# SW6124_A_B_C_Lighting_LED.net
KiCad netlist of a schematic drawn in Altium Designer
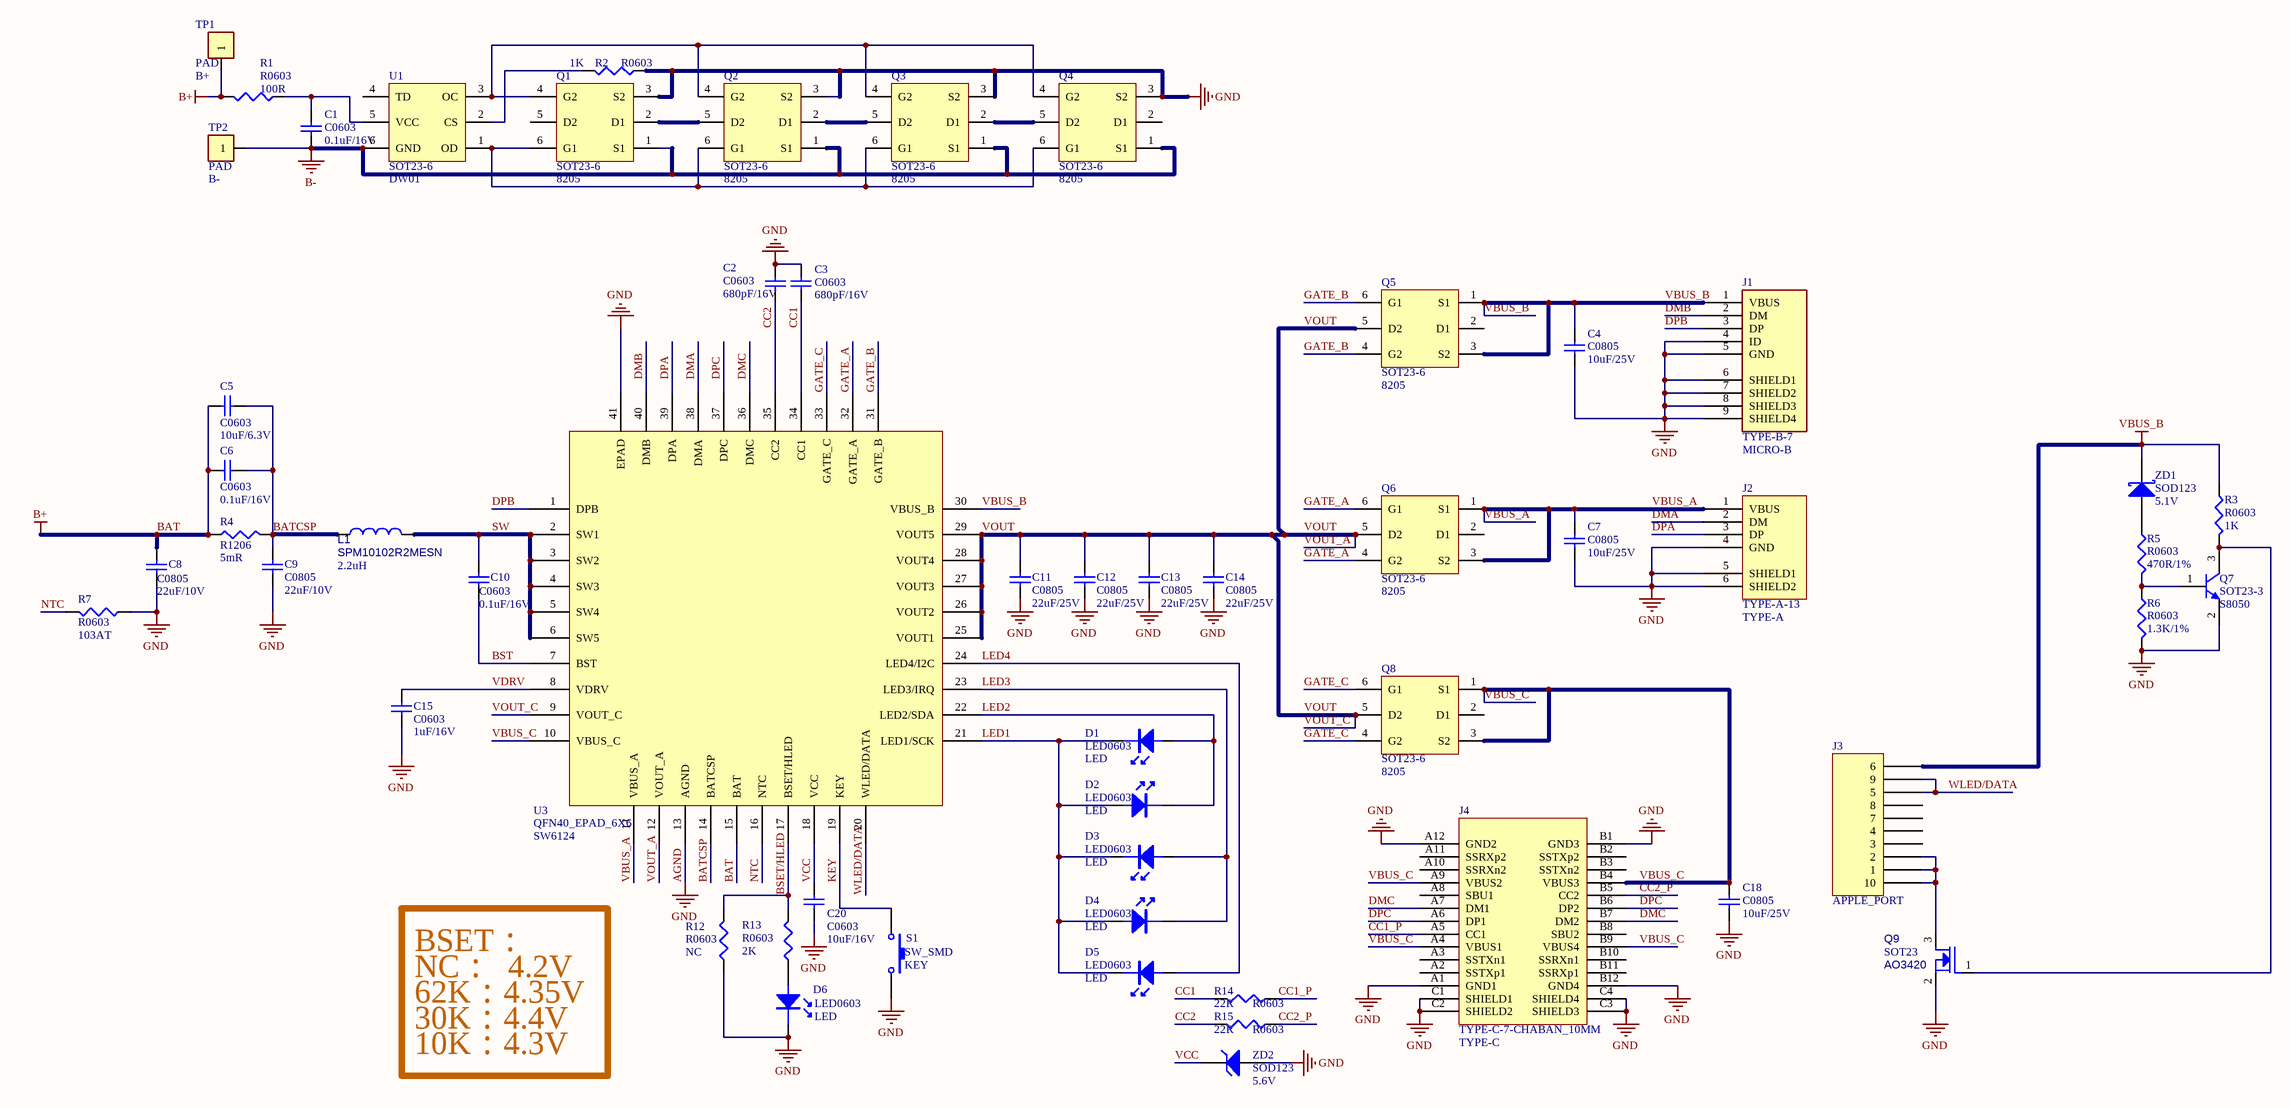
[diagram p0: SW6124+A+B+C+内部解密Lighting+LED.SchDoc]

(export (version "E")
  (design (tool "Eeschema 10.0.6"))
  (components
    (comp (ref "C1")
      (value "C0603")
      (footprint "C0603")
      (description "Capacitor")
      (fields (field (name "ALTIUM_VALUE") "0.1uF/16V") (field (name "PUBLISHER") "Altium Limited"))
      (libsource (lib "*") (part "Cap"))
    )
    (comp (ref "C2")
      (value "C0603")
      (footprint "C0603")
      (description "Capacitor")
      (fields (field (name "ALTIUM_VALUE") "680pF/16V") (field (name "PUBLISHER") "Altium Limited"))
      (libsource (lib "*") (part "CAP0603"))
    )
    (comp (ref "C3")
      (value "C0603")
      (footprint "C0603")
      (description "Capacitor")
      (fields (field (name "ALTIUM_VALUE") "680pF/16V") (field (name "PUBLISHER") "Altium Limited"))
      (libsource (lib "*") (part "CAP0603"))
    )
    (comp (ref "C4")
      (value "C0805")
      (footprint "C0805")
      (description "Capacitor")
      (fields (field (name "ALTIUM_VALUE") "10uF/25V") (field (name "PUBLISHER") "Altium Limited"))
      (libsource (lib "*") (part "CAP0603"))
    )
    (comp (ref "C5")
      (value "C0603")
      (footprint "C0603")
      (description "Capacitor")
      (fields (field (name "ALTIUM_VALUE") "10uF/6.3V") (field (name "PUBLISHER") "Altium Limited"))
      (libsource (lib "*") (part "CAP0603"))
    )
    (comp (ref "C6")
      (value "C0603")
      (footprint "C0603")
      (description "Capacitor")
      (fields (field (name "ALTIUM_VALUE") "0.1uF/16V") (field (name "PUBLISHER") "Altium Limited"))
      (libsource (lib "*") (part "CAP0603"))
    )
    (comp (ref "C7")
      (value "C0805")
      (footprint "C0805")
      (description "Capacitor")
      (fields (field (name "ALTIUM_VALUE") "10uF/25V") (field (name "PUBLISHER") "Altium Limited"))
      (libsource (lib "*") (part "CAP0603"))
    )
    (comp (ref "C8")
      (value "C0805")
      (footprint "C0805")
      (description "Capacitor")
      (fields (field (name "ALTIUM_VALUE") "22uF/10V") (field (name "PUBLISHER") "Altium Limited"))
      (libsource (lib "*") (part "CAP0805"))
    )
    (comp (ref "C9")
      (value "C0805")
      (footprint "C0805")
      (description "Capacitor")
      (fields (field (name "ALTIUM_VALUE") "22uF/10V") (field (name "PUBLISHER") "Altium Limited"))
      (libsource (lib "*") (part "CAP0805"))
    )
    (comp (ref "C10")
      (value "C0603")
      (footprint "C0603")
      (description "Capacitor")
      (fields (field (name "ALTIUM_VALUE") "0.1uF/16V") (field (name "PUBLISHER") "Altium Limited"))
      (libsource (lib "*") (part "CAP0603"))
    )
    (comp (ref "C11")
      (value "C0805")
      (footprint "C0805")
      (description "Capacitor")
      (fields (field (name "ALTIUM_VALUE") "22uF/25V") (field (name "PUBLISHER") "Altium Limited"))
      (libsource (lib "*") (part "CAP0805"))
    )
    (comp (ref "C12")
      (value "C0805")
      (footprint "C0805")
      (description "Capacitor")
      (fields (field (name "ALTIUM_VALUE") "22uF/25V") (field (name "PUBLISHER") "Altium Limited"))
      (libsource (lib "*") (part "CAP0805"))
    )
    (comp (ref "C13")
      (value "C0805")
      (footprint "C0805")
      (description "Capacitor")
      (fields (field (name "ALTIUM_VALUE") "22uF/25V") (field (name "PUBLISHER") "Altium Limited"))
      (libsource (lib "*") (part "CAP0805"))
    )
    (comp (ref "C14")
      (value "C0805")
      (footprint "C0805")
      (description "Capacitor")
      (fields (field (name "ALTIUM_VALUE") "22uF/25V") (field (name "PUBLISHER") "Altium Limited"))
      (libsource (lib "*") (part "CAP0805"))
    )
    (comp (ref "C15")
      (value "C0603")
      (footprint "C0603")
      (description "Capacitor")
      (fields (field (name "ALTIUM_VALUE") "1uF/16V") (field (name "PUBLISHER") "Altium Limited"))
      (libsource (lib "*") (part "CAP0603"))
    )
    (comp (ref "C18")
      (value "C0805")
      (footprint "C0805")
      (description "Capacitor")
      (fields (field (name "ALTIUM_VALUE") "10uF/25V") (field (name "PUBLISHER") "Altium Limited"))
      (libsource (lib "*") (part "CAP0603"))
    )
    (comp (ref "C20")
      (value "C0603")
      (footprint "C0603")
      (description "Capacitor")
      (fields (field (name "ALTIUM_VALUE") "10uF/16V") (field (name "PUBLISHER") "Altium Limited"))
      (libsource (lib "*") (part "CAP0603"))
    )
    (comp (ref "D1") (value "LED") (footprint "LED0603") (libsource (lib "*") (part "LED")))
    (comp (ref "D2") (value "LED") (footprint "LED0603") (libsource (lib "*") (part "LED")))
    (comp (ref "D3") (value "LED") (footprint "LED0603") (libsource (lib "*") (part "LED")))
    (comp (ref "D4") (value "LED") (footprint "LED0603") (libsource (lib "*") (part "LED")))
    (comp (ref "D5") (value "LED") (footprint "LED0603") (libsource (lib "*") (part "LED")))
    (comp (ref "D6") (value "LED") (footprint "LED0603") (libsource (lib "*") (part "LED")))
    (comp (ref "J1")
      (value "MICRO-B")
      (footprint "TYPE-B-7")
      (fields (field (name "FOOTPRINTF") "TYPE-B-7") (field (name "Comment") "USB_MICRO_B"))
      (libsource (lib "*") (part "USB_MICRO_B"))
    )
    (comp (ref "J2")
      (value "TYPE-A")
      (footprint "TYPE-A-13")
      (fields (field (name "FOOTPRINF") "TYPE-A-13") (field (name "Comment") "TYPE-A-1"))
      (libsource (lib "*") (part "TYPE-A-1"))
    )
    (comp (ref "J3") (value "APPLE_PORT") (libsource (lib "TEST") (part "APPLE_PORT")))
    (comp (ref "J4")
      (value "TYPE-C")
      (footprint "TYPE-C-7-CHABAN_10MM")
      (libsource (lib "*") (part "TYPE-C"))
    )
    (comp (ref "L1")
      (value "SPM10102R2MESN")
      (footprint "INDUCTOR_SPM1010")
      (fields (field (name "ALTIUM_VALUE") "2.2uH"))
      (libsource (lib "*") (part "INDUCTOR"))
    )
    (comp (ref "Q1")
      (value "8205")
      (footprint "SOT23-6")
      (fields (field (name "FOOTPRINF") "SOT23-6"))
      (libsource (lib "*") (part "8205B"))
    )
    (comp (ref "Q2")
      (value "8205")
      (footprint "SOT23-6")
      (fields (field (name "FOOTPRINF") "SOT23-6"))
      (libsource (lib "*") (part "8205B"))
    )
    (comp (ref "Q3")
      (value "8205")
      (footprint "SOT23-6")
      (fields (field (name "FOOTPRINF") "SOT23-6"))
      (libsource (lib "*") (part "8205B"))
    )
    (comp (ref "Q4")
      (value "8205")
      (footprint "SOT23-6")
      (fields (field (name "FOOTPRINF") "SOT23-6"))
      (libsource (lib "*") (part "8205B"))
    )
    (comp (ref "Q5")
      (value "8205")
      (footprint "SOT23-6")
      (fields (field (name "FOOTPRINF") "SOT23-6"))
      (libsource (lib "") (part "8205B_1"))
    )
    (comp (ref "Q6")
      (value "8205")
      (footprint "SOT23-6")
      (fields (field (name "FOOTPRINF") "SOT23-6"))
      (libsource (lib "") (part "8205B_1"))
    )
    (comp (ref "Q7")
      (value "S8050")
      (footprint "SOT23-3")
      (description "NPN General Purpose Amplifier")
      (fields (field (name "PUBLISHER") "Altium Limited"))
      (libsource (lib "Miscellaneous Devices") (part "2N3904"))
    )
    (comp (ref "Q8")
      (value "8205")
      (footprint "SOT23-6")
      (fields (field (name "FOOTPRINF") "SOT23-6"))
      (libsource (lib "") (part "8205B_1"))
    )
    (comp (ref "Q9") (value "AO3420") (footprint "SOT23") (libsource (lib "智融科技有限公司原理图库") (part "MOSFET_N")))
    (comp (ref "R1")
      (value "R0603")
      (footprint "R0603")
      (description "Resistor")
      (fields (field (name "ALTIUM_VALUE") "100R") (field (name "PUBLISHER") "Altium Limited"))
      (libsource (lib "*") (part "Res3"))
    )
    (comp (ref "R2")
      (value "R0603")
      (footprint "R0603")
      (description "Resistor")
      (fields (field (name "ALTIUM_VALUE") "1K") (field (name "PUBLISHER") "Altium Limited"))
      (libsource (lib "*") (part "Res3"))
    )
    (comp (ref "R3")
      (value "R0603")
      (footprint "R0603")
      (description "Resistor")
      (fields (field (name "ALTIUM_VALUE") "1K") (field (name "PUBLISHER") "Altium Limited"))
      (libsource (lib "Miscellaneous Devices") (part "Res3"))
    )
    (comp (ref "R4")
      (value "R1206")
      (footprint "R1206")
      (description "Resistor")
      (fields (field (name "ALTIUM_VALUE") "5mR") (field (name "PUBLISHER") "Altium Limited"))
      (libsource (lib "*") (part "RES"))
    )
    (comp (ref "R5")
      (value "R0603")
      (footprint "R0603")
      (description "Resistor")
      (fields (field (name "ALTIUM_VALUE") "470R/1%") (field (name "PUBLISHER") "Altium Limited"))
      (libsource (lib "Miscellaneous Devices") (part "Res3"))
    )
    (comp (ref "R6")
      (value "R0603")
      (footprint "R0603")
      (description "Resistor")
      (fields (field (name "ALTIUM_VALUE") "1.3K/1%") (field (name "PUBLISHER") "Altium Limited"))
      (libsource (lib "Miscellaneous Devices") (part "Res3"))
    )
    (comp (ref "R7")
      (value "R0603")
      (footprint "R0603")
      (description "Resistor")
      (fields (field (name "ALTIUM_VALUE") "103AT") (field (name "PUBLISHER") "Altium Limited"))
      (libsource (lib "*") (part "RES"))
    )
    (comp (ref "R12")
      (value "R0603")
      (footprint "R0603")
      (description "Resistor")
      (fields (field (name "ALTIUM_VALUE") "NC") (field (name "PUBLISHER") "Altium Limited"))
      (libsource (lib "*") (part "RES"))
    )
    (comp (ref "R13")
      (value "R0603")
      (footprint "R0603")
      (description "Resistor")
      (fields (field (name "ALTIUM_VALUE") "2K") (field (name "PUBLISHER") "Altium Limited"))
      (libsource (lib "*") (part "RES"))
    )
    (comp (ref "R14")
      (value "R0603")
      (footprint "R0603")
      (description "Resistor")
      (fields (field (name "ALTIUM_VALUE") "22R") (field (name "PUBLISHER") "Altium Limited"))
      (libsource (lib "*") (part "RES"))
    )
    (comp (ref "R15")
      (value "R0603")
      (footprint "R0603")
      (description "Resistor")
      (fields (field (name "ALTIUM_VALUE") "22R") (field (name "PUBLISHER") "Altium Limited"))
      (libsource (lib "*") (part "RES"))
    )
    (comp (ref "S1")
      (value "KEY")
      (footprint "SW_SMD")
      (fields (field (name "FOOTPRINF") "SW_SMD"))
      (libsource (lib "*") (part "SW K"))
    )
    (comp (ref "TP1") (value "B+") (footprint "PAD") (libsource (lib "*") (part "Test Point")))
    (comp (ref "TP2") (value "B-") (footprint "PAD") (libsource (lib "") (part "Test Point_1")))
    (comp (ref "U1")
      (value "DW01")
      (footprint "SOT23-6")
      (fields (field (name "FOOTPRINF") "SOT23-6"))
      (libsource (lib "*") (part "DW01"))
    )
    (comp (ref "U3")
      (value "SW6124")
      (footprint "QFN40_EPAD_6X6")
      (libsource (lib "TEST") (part "SW6106_AFC"))
    )
    (comp (ref "ZD1")
      (value "5.1V")
      (footprint "SOD123")
      (description "Schottky Rectifier")
      (fields (field (name "Comment") "Diode 11DQ03") (field (name "PUBLISHER") "Altium Limited"))
      (libsource (lib "Miscellaneous Devices") (part "Diode 11DQ03"))
    )
    (comp (ref "ZD2")
      (value "SOD123")
      (footprint "SOD-123")
      (description "Zener Diode")
      (fields (field (name "ALTIUM_UNNAMED_1") "5.6V"))
      (libsource (lib "Miscellaneous Devices") (part "D Zener"))
    )
  )
  (nets
    (net (code "1") (name "/BATCSP") (class "Default")
      (node (ref "C5") (pin "2") (pinfunction "2_2") (pintype "passive"))
      (node (ref "C6") (pin "2") (pinfunction "2_2") (pintype "passive"))
      (node (ref "C9") (pin "2") (pinfunction "2_2") (pintype "passive"))
      (node (ref "L1") (pin "1") (pinfunction "1_1") (pintype "passive"))
      (node (ref "R4") (pin "2") (pinfunction "2_2") (pintype "passive"))
      (node (ref "U3") (pin "14") (pinfunction "BATCSP_14") (pintype "passive"))
    )
    (net (code "2") (name "/BSET{slash}HLED") (class "Default")
      (node (ref "R12") (pin "2") (pinfunction "2_2") (pintype "passive"))
      (node (ref "R13") (pin "2") (pinfunction "2_2") (pintype "passive"))
      (node (ref "U3") (pin "17") (pinfunction "BSET/HLED_17") (pintype "passive"))
    )
    (net (code "3") (name "/BST") (class "Default")
      (node (ref "C10") (pin "1") (pinfunction "1_1") (pintype "passive"))
      (node (ref "U3") (pin "7") (pinfunction "BST_7") (pintype "passive"))
    )
    (net (code "4") (name "/CC1") (class "Default")
      (node (ref "C3") (pin "1") (pinfunction "1_1") (pintype "passive"))
      (node (ref "R14") (pin "2") (pinfunction "2_2") (pintype "passive"))
      (node (ref "U3") (pin "34") (pinfunction "CC1_34") (pintype "passive"))
    )
    (net (code "5") (name "/CC1_P") (class "Default")
      (node (ref "J4") (pin "A5") (pinfunction "CC1_A5") (pintype "passive"))
      (node (ref "R14") (pin "1") (pinfunction "1_1") (pintype "passive"))
    )
    (net (code "6") (name "/CC2") (class "Default")
      (node (ref "C2") (pin "1") (pinfunction "1_1") (pintype "passive"))
      (node (ref "R15") (pin "2") (pinfunction "2_2") (pintype "passive"))
      (node (ref "U3") (pin "35") (pinfunction "CC2_35") (pintype "passive"))
    )
    (net (code "7") (name "/CC2_P") (class "Default")
      (node (ref "J4") (pin "B5") (pinfunction "CC2_B5") (pintype "passive"))
      (node (ref "R15") (pin "1") (pinfunction "1_1") (pintype "passive"))
    )
    (net (code "8") (name "/DMA") (class "Default")
      (node (ref "J2") (pin "2") (pinfunction "DM_2") (pintype "passive"))
      (node (ref "U3") (pin "38") (pinfunction "DMA_38") (pintype "passive"))
    )
    (net (code "9") (name "/DMB") (class "Default")
      (node (ref "J1") (pin "2") (pinfunction "DM_2") (pintype "passive"))
      (node (ref "U3") (pin "40") (pinfunction "DMB_40") (pintype "passive"))
    )
    (net (code "10") (name "/DMC") (class "Default")
      (node (ref "J4") (pin "A7") (pinfunction "DM1_A7") (pintype "passive"))
      (node (ref "J4") (pin "B7") (pinfunction "DM2_B7") (pintype "passive"))
      (node (ref "U3") (pin "36") (pinfunction "DMC_36") (pintype "passive"))
    )
    (net (code "11") (name "/DPA") (class "Default")
      (node (ref "J2") (pin "3") (pinfunction "DP_3") (pintype "passive"))
      (node (ref "U3") (pin "39") (pinfunction "DPA_39") (pintype "passive"))
    )
    (net (code "12") (name "/DPB") (class "Default")
      (node (ref "J1") (pin "3") (pinfunction "DP_3") (pintype "passive"))
      (node (ref "U3") (pin "1") (pinfunction "DPB_1") (pintype "passive"))
    )
    (net (code "13") (name "/DPC") (class "Default")
      (node (ref "J4") (pin "A6") (pinfunction "DP1_A6") (pintype "passive"))
      (node (ref "J4") (pin "B6") (pinfunction "DP2_B6") (pintype "passive"))
      (node (ref "U3") (pin "37") (pinfunction "DPC_37") (pintype "passive"))
    )
    (net (code "14") (name "/GATE_A") (class "Default")
      (node (ref "Q6") (pin "4") (pinfunction "G2_4") (pintype "passive"))
      (node (ref "Q6") (pin "6") (pinfunction "G1_6") (pintype "passive"))
      (node (ref "U3") (pin "32") (pinfunction "GATE_A_32") (pintype "passive"))
    )
    (net (code "15") (name "/GATE_B") (class "Default")
      (node (ref "Q5") (pin "4") (pinfunction "G2_4") (pintype "passive"))
      (node (ref "Q5") (pin "6") (pinfunction "G1_6") (pintype "passive"))
      (node (ref "U3") (pin "31") (pinfunction "GATE_B_31") (pintype "passive"))
    )
    (net (code "16") (name "/GATE_C") (class "Default")
      (node (ref "Q8") (pin "4") (pinfunction "G2_4") (pintype "passive"))
      (node (ref "Q8") (pin "6") (pinfunction "G1_6") (pintype "passive"))
      (node (ref "U3") (pin "33") (pinfunction "GATE_C_33") (pintype "passive"))
    )
    (net (code "17") (name "/KEY") (class "Default")
      (node (ref "S1") (pin "1") (pinfunction "1_1") (pintype "passive"))
      (node (ref "U3") (pin "19") (pinfunction "KEY_19") (pintype "passive"))
    )
    (net (code "18") (name "/LED1") (class "Default")
      (node (ref "D1") (pin "2") (pinfunction "K_2") (pintype "passive"))
      (node (ref "D2") (pin "1") (pinfunction "A_1") (pintype "passive"))
      (node (ref "D3") (pin "2") (pinfunction "K_2") (pintype "passive"))
      (node (ref "D4") (pin "1") (pinfunction "A_1") (pintype "passive"))
      (node (ref "D5") (pin "2") (pinfunction "K_2") (pintype "passive"))
      (node (ref "U3") (pin "21") (pinfunction "LED1/SCK_21") (pintype "passive"))
    )
    (net (code "19") (name "/LED2") (class "Default")
      (node (ref "D1") (pin "1") (pinfunction "A_1") (pintype "passive"))
      (node (ref "D2") (pin "2") (pinfunction "K_2") (pintype "passive"))
      (node (ref "U3") (pin "22") (pinfunction "LED2/SDA_22") (pintype "passive"))
    )
    (net (code "20") (name "/LED3") (class "Default")
      (node (ref "D3") (pin "1") (pinfunction "A_1") (pintype "passive"))
      (node (ref "D4") (pin "2") (pinfunction "K_2") (pintype "passive"))
      (node (ref "U3") (pin "23") (pinfunction "LED3/IRQ_23") (pintype "passive"))
    )
    (net (code "21") (name "/LED4") (class "Default")
      (node (ref "D5") (pin "1") (pinfunction "A_1") (pintype "passive"))
      (node (ref "U3") (pin "24") (pinfunction "LED4/I2C_24") (pintype "passive"))
    )
    (net (code "22") (name "/NTC") (class "Default")
      (node (ref "R7") (pin "2") (pinfunction "2_2") (pintype "passive"))
      (node (ref "U3") (pin "16") (pinfunction "NTC_16") (pintype "passive"))
    )
    (net (code "23") (name "/SW") (class "Default")
      (node (ref "C10") (pin "2") (pinfunction "2_2") (pintype "passive"))
      (node (ref "L1") (pin "2") (pinfunction "2_2") (pintype "passive"))
      (node (ref "U3") (pin "2") (pinfunction "SW1_2") (pintype "passive"))
      (node (ref "U3") (pin "3") (pinfunction "SW2_3") (pintype "passive"))
      (node (ref "U3") (pin "4") (pinfunction "SW3_4") (pintype "passive"))
      (node (ref "U3") (pin "5") (pinfunction "SW4_5") (pintype "passive"))
      (node (ref "U3") (pin "6") (pinfunction "SW5_6") (pintype "passive"))
    )
    (net (code "24") (name "/VBUS_A") (class "Default")
      (node (ref "C7") (pin "2") (pinfunction "2_2") (pintype "passive"))
      (node (ref "J2") (pin "1") (pinfunction "VBUS_1") (pintype "passive"))
      (node (ref "Q6") (pin "1") (pinfunction "S1_1") (pintype "passive"))
      (node (ref "Q6") (pin "3") (pinfunction "S2_3") (pintype "passive"))
      (node (ref "U3") (pin "11") (pinfunction "VBUS_A_11") (pintype "passive"))
    )
    (net (code "25") (name "/VBUS_C") (class "Default")
      (node (ref "C18") (pin "2") (pinfunction "2_2") (pintype "passive"))
      (node (ref "J4") (pin "A4") (pinfunction "VBUS1_A4") (pintype "passive"))
      (node (ref "J4") (pin "A9") (pinfunction "VBUS2_A9") (pintype "passive"))
      (node (ref "J4") (pin "B4") (pinfunction "VBUS3_B4") (pintype "passive"))
      (node (ref "J4") (pin "B9") (pinfunction "VBUS4_B9") (pintype "passive"))
      (node (ref "Q8") (pin "1") (pinfunction "S1_1") (pintype "passive"))
      (node (ref "Q8") (pin "3") (pinfunction "S2_3") (pintype "passive"))
      (node (ref "U3") (pin "10") (pinfunction "VBUS_C_10") (pintype "passive"))
    )
    (net (code "26") (name "/VCC") (class "Default")
      (node (ref "C20") (pin "2") (pinfunction "2_2") (pintype "passive"))
      (node (ref "U3") (pin "18") (pinfunction "VCC_18") (pintype "passive"))
      (node (ref "ZD2") (pin "2") (pinfunction "K_2") (pintype "passive"))
    )
    (net (code "27") (name "/VDRV") (class "Default")
      (node (ref "C15") (pin "2") (pinfunction "2_2") (pintype "passive"))
      (node (ref "U3") (pin "8") (pinfunction "VDRV_8") (pintype "passive"))
    )
    (net (code "28") (name "/VOUT") (class "Default")
      (node (ref "C11") (pin "2") (pinfunction "2_2") (pintype "passive"))
      (node (ref "C12") (pin "2") (pinfunction "2_2") (pintype "passive"))
      (node (ref "C13") (pin "2") (pinfunction "2_2") (pintype "passive"))
      (node (ref "C14") (pin "2") (pinfunction "2_2") (pintype "passive"))
      (node (ref "Q5") (pin "5") (pinfunction "D2_5") (pintype "passive"))
      (node (ref "Q6") (pin "5") (pinfunction "D2_5") (pintype "passive"))
      (node (ref "Q8") (pin "5") (pinfunction "D2_5") (pintype "passive"))
      (node (ref "U3") (pin "12") (pinfunction "VOUT_A_12") (pintype "passive"))
      (node (ref "U3") (pin "25") (pinfunction "VOUT1_25") (pintype "passive"))
      (node (ref "U3") (pin "26") (pinfunction "VOUT2_26") (pintype "passive"))
      (node (ref "U3") (pin "27") (pinfunction "VOUT3_27") (pintype "passive"))
      (node (ref "U3") (pin "28") (pinfunction "VOUT4_28") (pintype "passive"))
      (node (ref "U3") (pin "29") (pinfunction "VOUT5_29") (pintype "passive"))
      (node (ref "U3") (pin "9") (pinfunction "VOUT_C_9") (pintype "passive"))
    )
    (net (code "29") (name "/WLED{slash}DATA") (class "Default")
      (node (ref "J3") (pin "5") (pinfunction "5_5") (pintype "passive"))
      (node (ref "J3") (pin "9") (pinfunction "9_9") (pintype "passive"))
      (node (ref "U3") (pin "20") (pinfunction "WLED/DATA_20") (pintype "passive"))
    )
    (net (code "30") (name "B+") (class "Default")
      (node (ref "C5") (pin "1") (pinfunction "1_1") (pintype "passive"))
      (node (ref "C6") (pin "1") (pinfunction "1_1") (pintype "passive"))
      (node (ref "C8") (pin "2") (pinfunction "2_2") (pintype "passive"))
      (node (ref "R1") (pin "2") (pinfunction "2_2") (pintype "passive"))
      (node (ref "R4") (pin "1") (pinfunction "1_1") (pintype "passive"))
      (node (ref "TP1") (pin "1") (pinfunction "1_1") (pintype "passive"))
      (node (ref "U3") (pin "15") (pinfunction "BAT_15") (pintype "passive"))
    )
    (net (code "31") (name "B-") (class "Default")
      (node (ref "C1") (pin "1") (pinfunction "1_1") (pintype "passive"))
      (node (ref "Q1") (pin "1") (pinfunction "S1_1") (pintype "passive"))
      (node (ref "Q2") (pin "1") (pinfunction "S1_1") (pintype "passive"))
      (node (ref "Q3") (pin "1") (pinfunction "S1_1") (pintype "passive"))
      (node (ref "Q4") (pin "1") (pinfunction "S1_1") (pintype "passive"))
      (node (ref "TP2") (pin "1") (pinfunction "1_1") (pintype "passive"))
      (node (ref "U1") (pin "6") (pinfunction "GND_6") (pintype "passive"))
    )
    (net (code "32") (name "GND") (class "Default")
      (node (ref "C11") (pin "1") (pinfunction "1_1") (pintype "passive"))
      (node (ref "C12") (pin "1") (pinfunction "1_1") (pintype "passive"))
      (node (ref "C13") (pin "1") (pinfunction "1_1") (pintype "passive"))
      (node (ref "C14") (pin "1") (pinfunction "1_1") (pintype "passive"))
      (node (ref "C15") (pin "1") (pinfunction "1_1") (pintype "passive"))
      (node (ref "C18") (pin "1") (pinfunction "1_1") (pintype "passive"))
      (node (ref "C2") (pin "2") (pinfunction "2_2") (pintype "passive"))
      (node (ref "C20") (pin "1") (pinfunction "1_1") (pintype "passive"))
      (node (ref "C3") (pin "2") (pinfunction "2_2") (pintype "passive"))
      (node (ref "C4") (pin "1") (pinfunction "1_1") (pintype "passive"))
      (node (ref "C7") (pin "1") (pinfunction "1_1") (pintype "passive"))
      (node (ref "C8") (pin "1") (pinfunction "1_1") (pintype "passive"))
      (node (ref "C9") (pin "1") (pinfunction "1_1") (pintype "passive"))
      (node (ref "D6") (pin "2") (pinfunction "K_2") (pintype "passive"))
      (node (ref "J1") (pin "4") (pinfunction "ID_4") (pintype "passive"))
      (node (ref "J1") (pin "5") (pinfunction "GND_5") (pintype "passive"))
      (node (ref "J1") (pin "6") (pinfunction "SHIELD1_6") (pintype "passive"))
      (node (ref "J1") (pin "7") (pinfunction "SHIELD2_7") (pintype "passive"))
      (node (ref "J1") (pin "8") (pinfunction "SHIELD3_8") (pintype "passive"))
      (node (ref "J1") (pin "9") (pinfunction "SHIELD4_9") (pintype "passive"))
      (node (ref "J2") (pin "4") (pinfunction "GND_4") (pintype "passive"))
      (node (ref "J2") (pin "5") (pinfunction "SHIELD1_5") (pintype "passive"))
      (node (ref "J2") (pin "6") (pinfunction "SHIELD2_6") (pintype "passive"))
      (node (ref "J4") (pin "A1") (pinfunction "GND1_A1") (pintype "passive"))
      (node (ref "J4") (pin "A12") (pinfunction "GND2_A12") (pintype "passive"))
      (node (ref "J4") (pin "B1") (pinfunction "GND3_B1") (pintype "passive"))
      (node (ref "J4") (pin "B12") (pinfunction "GND4_B12") (pintype "passive"))
      (node (ref "J4") (pin "C1") (pinfunction "SHIELD1_C1") (pintype "passive"))
      (node (ref "J4") (pin "C2") (pinfunction "SHIELD2_C2") (pintype "passive"))
      (node (ref "J4") (pin "C3") (pinfunction "SHIELD3_C3") (pintype "passive"))
      (node (ref "J4") (pin "C4") (pinfunction "SHIELD4_C4") (pintype "passive"))
      (node (ref "Q1") (pin "3") (pinfunction "S2_3") (pintype "passive"))
      (node (ref "Q2") (pin "3") (pinfunction "S2_3") (pintype "passive"))
      (node (ref "Q3") (pin "3") (pinfunction "S2_3") (pintype "passive"))
      (node (ref "Q4") (pin "3") (pinfunction "S2_3") (pintype "passive"))
      (node (ref "Q7") (pin "2") (pinfunction "E_2") (pintype "passive"))
      (node (ref "Q9") (pin "2") (pinfunction "SOURCE_2") (pintype "passive"))
      (node (ref "R12") (pin "1") (pinfunction "1_1") (pintype "passive"))
      (node (ref "R2") (pin "1") (pinfunction "1_1") (pintype "passive"))
      (node (ref "R6") (pin "2") (pinfunction "2_2") (pintype "passive"))
      (node (ref "R7") (pin "1") (pinfunction "1_1") (pintype "passive"))
      (node (ref "S1") (pin "2") (pinfunction "2_2") (pintype "passive"))
      (node (ref "U3") (pin "13") (pinfunction "AGND_13") (pintype "passive"))
      (node (ref "U3") (pin "41") (pinfunction "EPAD_41") (pintype "passive"))
      (node (ref "ZD2") (pin "1") (pinfunction "A_1") (pintype "passive"))
    )
    (net (code "33") (name "Net-(D6-A)") (class "Default")
      (node (ref "D6") (pin "1") (pinfunction "A_1") (pintype "passive"))
      (node (ref "R13") (pin "1") (pinfunction "1_1") (pintype "passive"))
    )
    (net (code "34") (name "Net-(Q1-D1)") (class "Default")
      (node (ref "Q1") (pin "2") (pinfunction "D1_2") (pintype "passive"))
      (node (ref "Q2") (pin "5") (pinfunction "D2_5") (pintype "passive"))
    )
    (net (code "35") (name "Net-(Q1-G1)") (class "Default")
      (node (ref "Q1") (pin "6") (pinfunction "G1_6") (pintype "passive"))
      (node (ref "Q2") (pin "6") (pinfunction "G1_6") (pintype "passive"))
      (node (ref "Q3") (pin "6") (pinfunction "G1_6") (pintype "passive"))
      (node (ref "Q4") (pin "6") (pinfunction "G1_6") (pintype "passive"))
      (node (ref "U1") (pin "1") (pinfunction "OD_1") (pintype "passive"))
    )
    (net (code "36") (name "Net-(Q1-G2)") (class "Default")
      (node (ref "Q1") (pin "4") (pinfunction "G2_4") (pintype "passive"))
      (node (ref "Q2") (pin "4") (pinfunction "G2_4") (pintype "passive"))
      (node (ref "Q3") (pin "4") (pinfunction "G2_4") (pintype "passive"))
      (node (ref "Q4") (pin "4") (pinfunction "G2_4") (pintype "passive"))
      (node (ref "U1") (pin "3") (pinfunction "OC_3") (pintype "passive"))
    )
    (net (code "37") (name "Net-(Q2-D1)") (class "Default")
      (node (ref "Q2") (pin "2") (pinfunction "D1_2") (pintype "passive"))
      (node (ref "Q3") (pin "5") (pinfunction "D2_5") (pintype "passive"))
    )
    (net (code "38") (name "Net-(Q3-D1)") (class "Default")
      (node (ref "Q3") (pin "2") (pinfunction "D1_2") (pintype "passive"))
      (node (ref "Q4") (pin "5") (pinfunction "D2_5") (pintype "passive"))
    )
    (net (code "39") (name "Net-(Q7-B)") (class "Default")
      (node (ref "Q7") (pin "1") (pinfunction "B_1") (pintype "passive"))
      (node (ref "R5") (pin "2") (pinfunction "2_2") (pintype "passive"))
      (node (ref "R6") (pin "1") (pinfunction "1_1") (pintype "passive"))
    )
    (net (code "40") (name "Net-(Q7-C)") (class "Default")
      (node (ref "Q7") (pin "3") (pinfunction "C_3") (pintype "passive"))
      (node (ref "Q9") (pin "1") (pinfunction "GATE_1") (pintype "passive"))
      (node (ref "R3") (pin "2") (pinfunction "2_2") (pintype "passive"))
    )
    (net (code "41") (name "Net-(Q9-DRAIN)") (class "Default")
      (node (ref "J3") (pin "1") (pinfunction "1_1") (pintype "passive"))
      (node (ref "J3") (pin "10") (pinfunction "10_10") (pintype "passive"))
      (node (ref "J3") (pin "2") (pinfunction "2_2") (pintype "passive"))
      (node (ref "Q9") (pin "3") (pinfunction "DRAIN_3") (pintype "passive"))
    )
    (net (code "42") (name "Net-(U1-CS)") (class "Default")
      (node (ref "R2") (pin "2") (pinfunction "2_2") (pintype "passive"))
      (node (ref "U1") (pin "2") (pinfunction "CS_2") (pintype "passive"))
    )
    (net (code "43") (name "Net-(U1-VCC)") (class "Default")
      (node (ref "C1") (pin "2") (pinfunction "2_2") (pintype "passive"))
      (node (ref "R1") (pin "1") (pinfunction "1_1") (pintype "passive"))
      (node (ref "U1") (pin "5") (pinfunction "VCC_5") (pintype "passive"))
    )
    (net (code "44") (name "Net-(ZD1-A)") (class "Default")
      (node (ref "R5") (pin "1") (pinfunction "1_1") (pintype "passive"))
      (node (ref "ZD1") (pin "1") (pinfunction "A_1") (pintype "passive"))
    )
    (net (code "45") (name "VBUS_B") (class "Default")
      (node (ref "C4") (pin "2") (pinfunction "2_2") (pintype "passive"))
      (node (ref "J1") (pin "1") (pinfunction "VBUS_1") (pintype "passive"))
      (node (ref "J3") (pin "6") (pinfunction "6_6") (pintype "passive"))
      (node (ref "Q5") (pin "1") (pinfunction "S1_1") (pintype "passive"))
      (node (ref "Q5") (pin "3") (pinfunction "S2_3") (pintype "passive"))
      (node (ref "R3") (pin "1") (pinfunction "1_1") (pintype "passive"))
      (node (ref "U3") (pin "30") (pinfunction "VBUS_B_30") (pintype "passive"))
      (node (ref "ZD1") (pin "2") (pinfunction "K_2") (pintype "passive"))
    )
    (net (code "46") (name "unconnected-(J3-Pad3)") (class "Default")
      (node (ref "J3") (pin "3") (pinfunction "3_3") (pintype "passive"))
    )
    (net (code "47") (name "unconnected-(J3-Pad4)") (class "Default")
      (node (ref "J3") (pin "4") (pinfunction "4_4") (pintype "passive"))
    )
    (net (code "48") (name "unconnected-(J3-Pad7)") (class "Default")
      (node (ref "J3") (pin "7") (pinfunction "7_7") (pintype "passive"))
    )
    (net (code "49") (name "unconnected-(J3-Pad8)") (class "Default")
      (node (ref "J3") (pin "8") (pinfunction "8_8") (pintype "passive"))
    )
    (net (code "50") (name "unconnected-(J4-SBU1-PadA8)") (class "Default")
      (node (ref "J4") (pin "A8") (pinfunction "SBU1_A8") (pintype "passive"))
    )
    (net (code "51") (name "unconnected-(J4-SBU2-PadB8)") (class "Default")
      (node (ref "J4") (pin "B8") (pinfunction "SBU2_B8") (pintype "passive"))
    )
    (net (code "52") (name "unconnected-(J4-SSRXn1-PadB10)") (class "Default")
      (node (ref "J4") (pin "B10") (pinfunction "SSRXn1_B10") (pintype "passive"))
    )
    (net (code "53") (name "unconnected-(J4-SSRXn2-PadA10)") (class "Default")
      (node (ref "J4") (pin "A10") (pinfunction "SSRXn2_A10") (pintype "passive"))
    )
    (net (code "54") (name "unconnected-(J4-SSRXp1-PadB11)") (class "Default")
      (node (ref "J4") (pin "B11") (pinfunction "SSRXp1_B11") (pintype "passive"))
    )
    (net (code "55") (name "unconnected-(J4-SSRXp2-PadA11)") (class "Default")
      (node (ref "J4") (pin "A11") (pinfunction "SSRXp2_A11") (pintype "passive"))
    )
    (net (code "56") (name "unconnected-(J4-SSTXn1-PadA3)") (class "Default")
      (node (ref "J4") (pin "A3") (pinfunction "SSTXn1_A3") (pintype "passive"))
    )
    (net (code "57") (name "unconnected-(J4-SSTXn2-PadB3)") (class "Default")
      (node (ref "J4") (pin "B3") (pinfunction "SSTXn2_B3") (pintype "passive"))
    )
    (net (code "58") (name "unconnected-(J4-SSTXp1-PadA2)") (class "Default")
      (node (ref "J4") (pin "A2") (pinfunction "SSTXp1_A2") (pintype "passive"))
    )
    (net (code "59") (name "unconnected-(J4-SSTXp2-PadB2)") (class "Default")
      (node (ref "J4") (pin "B2") (pinfunction "SSTXp2_B2") (pintype "passive"))
    )
    (net (code "60") (name "unconnected-(Q1-D2-Pad5)") (class "Default")
      (node (ref "Q1") (pin "5") (pinfunction "D2_5") (pintype "passive"))
    )
    (net (code "61") (name "unconnected-(Q4-D1-Pad2)") (class "Default")
      (node (ref "Q4") (pin "2") (pinfunction "D1_2") (pintype "passive"))
    )
    (net (code "62") (name "unconnected-(Q5-D1-Pad2)") (class "Default")
      (node (ref "Q5") (pin "2") (pinfunction "D1_2") (pintype "passive"))
    )
    (net (code "63") (name "unconnected-(Q6-D1-Pad2)") (class "Default")
      (node (ref "Q6") (pin "2") (pinfunction "D1_2") (pintype "passive"))
    )
    (net (code "64") (name "unconnected-(Q8-D1-Pad2)") (class "Default")
      (node (ref "Q8") (pin "2") (pinfunction "D1_2") (pintype "passive"))
    )
    (net (code "65") (name "unconnected-(U1-TD-Pad4)") (class "Default")
      (node (ref "U1") (pin "4") (pinfunction "TD_4") (pintype "passive"))
    )
  )
)
